# LipSync_Joystick_Board.net
KiCad netlist of a schematic drawn in EAGLE
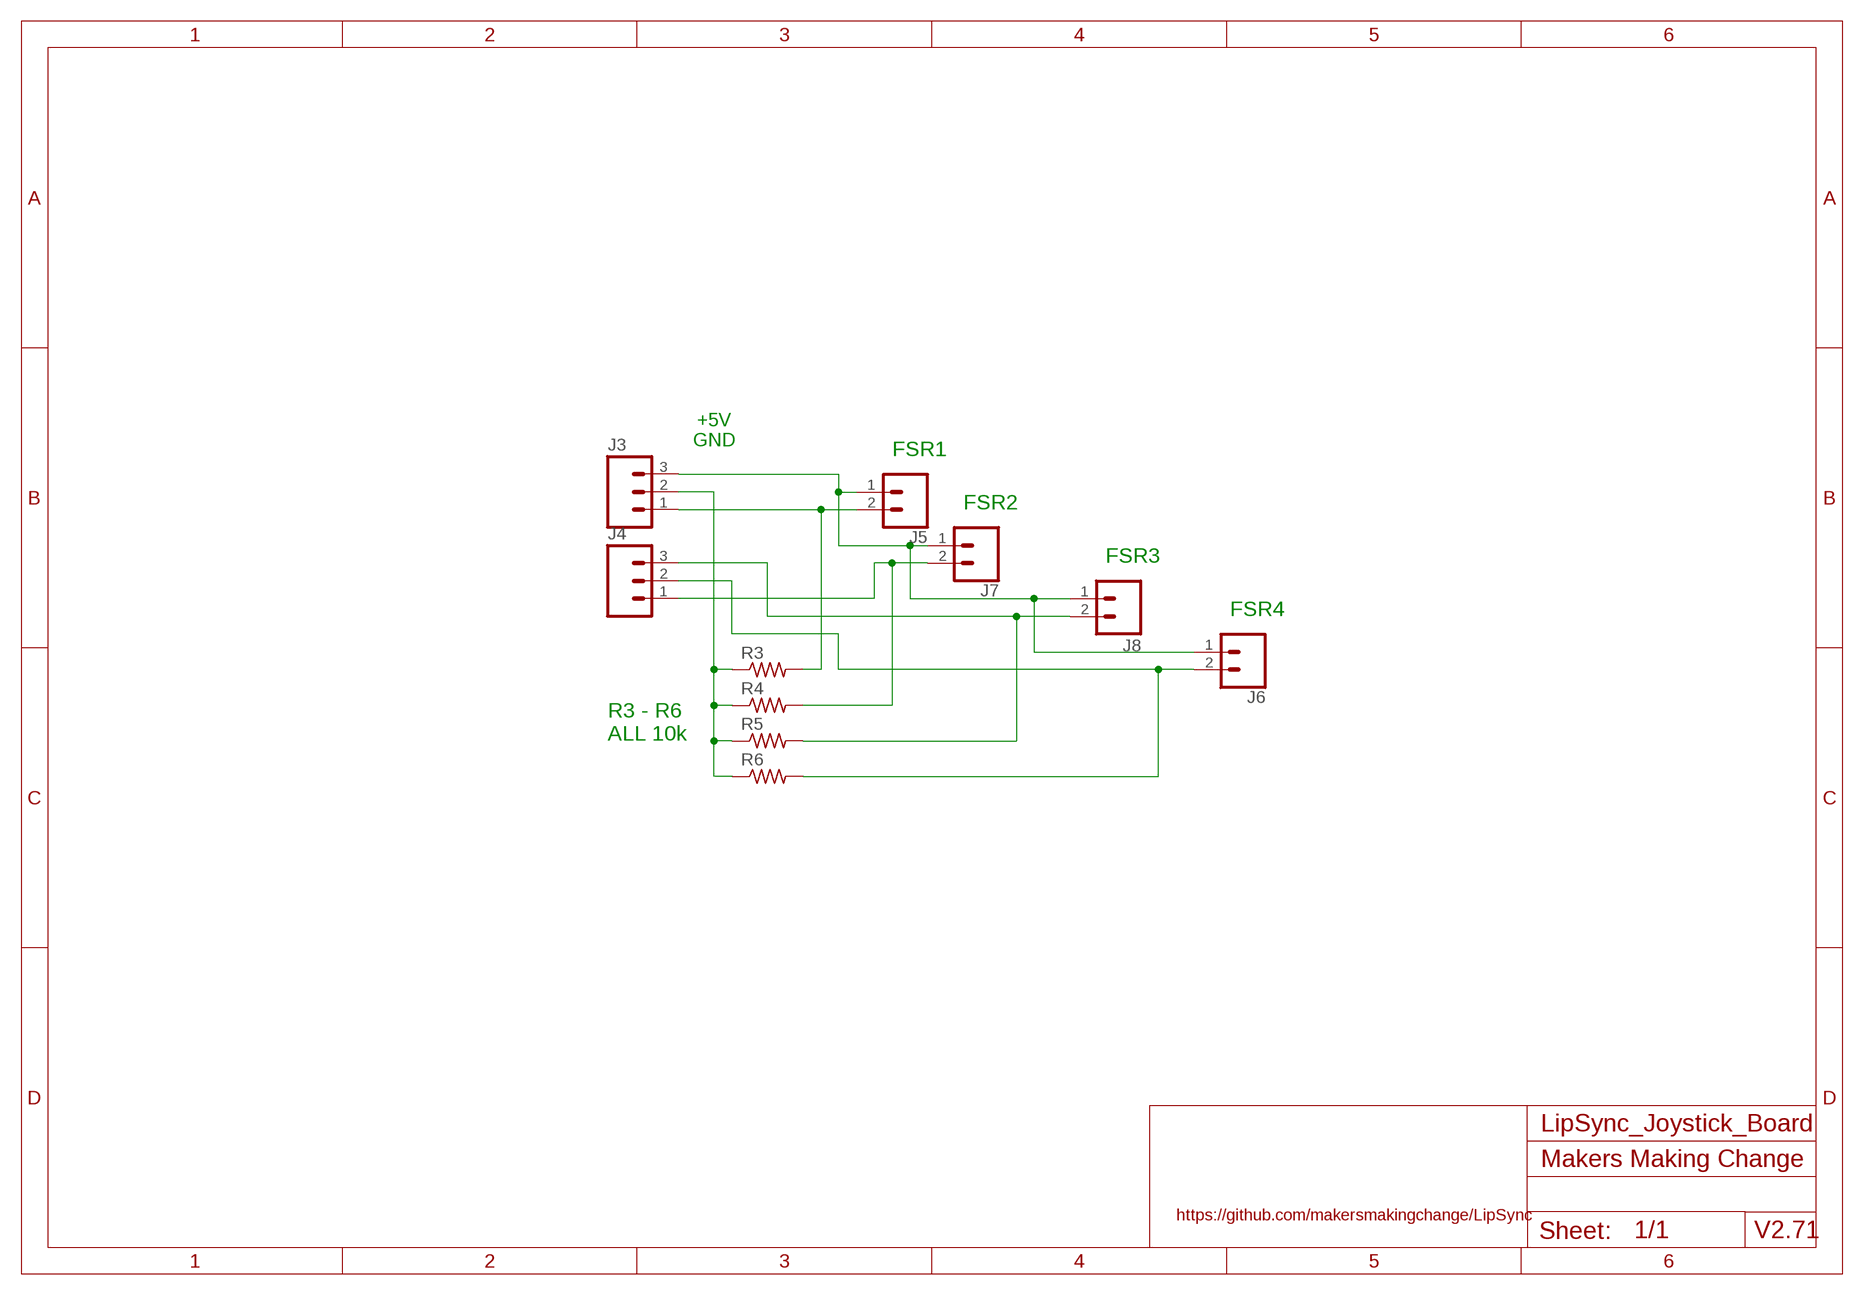
[diagram p0: schematic, sheet 1]

(export (version "E")
  (design (tool "Eeschema 10.0.6"))
  (components
    (comp (ref "J3")
      (value "M03LOCK")
      (footprint "eagle-import:1X03_LOCK")
      (libsource (lib "eagle-import") (part "M03LOCK"))
    )
    (comp (ref "J4")
      (value "M03LOCK")
      (footprint "eagle-import:1X03_LOCK")
      (libsource (lib "eagle-import") (part "M03LOCK"))
    )
    (comp (ref "J5")
      (value "CONN_02PTH3")
      (footprint "eagle-import:1X02_LONGPADS")
      (libsource (lib "eagle-import") (part "CONN_02PTH3"))
    )
    (comp (ref "J6")
      (value "CONN_02PTH3")
      (footprint "eagle-import:1X02_LONGPADS")
      (libsource (lib "eagle-import") (part "CONN_02PTH3"))
    )
    (comp (ref "J7")
      (value "CONN_02PTH3")
      (footprint "eagle-import:1X02_LONGPADS")
      (libsource (lib "eagle-import") (part "CONN_02PTH3"))
    )
    (comp (ref "J8")
      (value "M02PTH3")
      (footprint "eagle-import:1X02_LONGPADS@1")
      (libsource (lib "eagle-import") (part "M02PTH3"))
    )
    (comp (ref "R3")
      (value "R-US_0204/5")
      (footprint "eagle-import:0204_5")
      (libsource (lib "eagle-import") (part "R-US_0204/5"))
    )
    (comp (ref "R4")
      (value "R-US_0204/5")
      (footprint "eagle-import:0204_5")
      (libsource (lib "eagle-import") (part "R-US_0204/5"))
    )
    (comp (ref "R5")
      (value "R-US_0204/5")
      (footprint "eagle-import:0204_5")
      (libsource (lib "eagle-import") (part "R-US_0204/5"))
    )
    (comp (ref "R6")
      (value "R-US_0204/5")
      (footprint "eagle-import:0204_5")
      (libsource (lib "eagle-import") (part "R-US_0204/5"))
    )
  )
  (nets
    (net (code "1") (name "Net-(J3-Pad1)") (class "Default")
      (node (ref "J3") (pin "1") (pinfunction "1_1") (pintype "passive"))
      (node (ref "J5") (pin "2") (pinfunction "2_2") (pintype "passive"))
      (node (ref "R3") (pin "2") (pinfunction "2_2") (pintype "passive"))
    )
    (net (code "2") (name "Net-(J3-Pad2)") (class "Default")
      (node (ref "J3") (pin "2") (pinfunction "2_2") (pintype "passive"))
      (node (ref "R3") (pin "1") (pinfunction "1_1") (pintype "passive"))
      (node (ref "R4") (pin "1") (pinfunction "1_1") (pintype "passive"))
      (node (ref "R5") (pin "1") (pinfunction "1_1") (pintype "passive"))
      (node (ref "R6") (pin "1") (pinfunction "1_1") (pintype "passive"))
    )
    (net (code "3") (name "Net-(J3-Pad3)") (class "Default")
      (node (ref "J3") (pin "3") (pinfunction "3_3") (pintype "passive"))
      (node (ref "J5") (pin "1") (pinfunction "1_1") (pintype "passive"))
      (node (ref "J6") (pin "1") (pinfunction "1_1") (pintype "passive"))
      (node (ref "J7") (pin "1") (pinfunction "1_1") (pintype "passive"))
      (node (ref "J8") (pin "1") (pinfunction "1_1") (pintype "passive"))
    )
    (net (code "4") (name "Net-(J4-Pad1)") (class "Default")
      (node (ref "J4") (pin "1") (pinfunction "1_1") (pintype "passive"))
      (node (ref "J7") (pin "2") (pinfunction "2_2") (pintype "passive"))
      (node (ref "R4") (pin "2") (pinfunction "2_2") (pintype "passive"))
    )
    (net (code "5") (name "Net-(J4-Pad2)") (class "Default")
      (node (ref "J4") (pin "2") (pinfunction "2_2") (pintype "passive"))
      (node (ref "J6") (pin "2") (pinfunction "2_2") (pintype "passive"))
      (node (ref "R6") (pin "2") (pinfunction "2_2") (pintype "passive"))
    )
    (net (code "6") (name "Net-(J4-Pad3)") (class "Default")
      (node (ref "J4") (pin "3") (pinfunction "3_3") (pintype "passive"))
      (node (ref "J8") (pin "2") (pinfunction "2_2") (pintype "passive"))
      (node (ref "R5") (pin "2") (pinfunction "2_2") (pintype "passive"))
    )
  )
)
